# PIC18_breakout.net
KiCad netlist of a schematic drawn in EAGLE
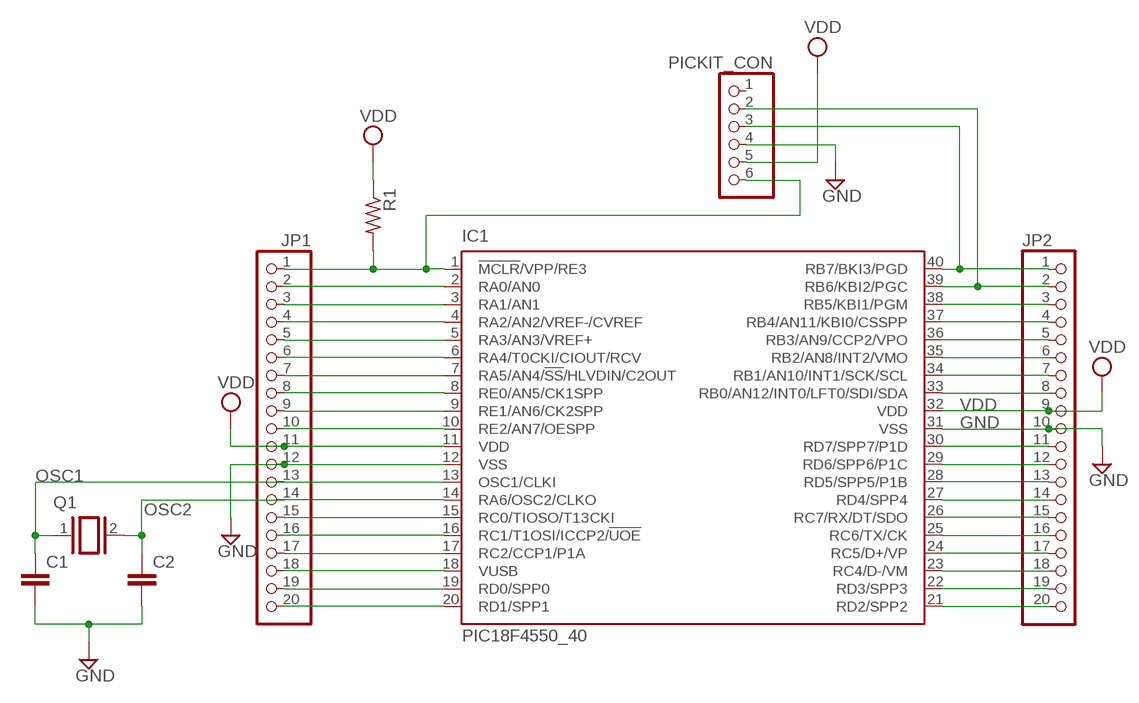
[diagram p0: schematic, sheet 1]

(export (version "E")
  (design (tool "Eeschema 10.0.6"))
  (components
    (comp (ref "C1")
      (value "C-EU075-032X103")
      (footprint "eagle-import:C075-032X103")
      (libsource (lib "eagle-import") (part "C-EU075-032X103"))
    )
    (comp (ref "C2")
      (value "C-EU075-032X103")
      (footprint "eagle-import:C075-032X103")
      (libsource (lib "eagle-import") (part "C-EU075-032X103"))
    )
    (comp (ref "IC1")
      (value "PIC18F4550_40")
      (footprint "eagle-import:DIL40")
      (fields (field (name "MF") "MICROCHIP") (field (name "MPN") "PIC18F4550-I/P"))
      (libsource (lib "eagle-import") (part "PIC18F4_40550"))
    )
    (comp (ref "JP1")
      (value "PINHD-1X20")
      (footprint "eagle-import:1X20")
      (libsource (lib "eagle-import") (part "PINHD-1X20"))
    )
    (comp (ref "JP2")
      (value "PINHD-1X20")
      (footprint "eagle-import:1X20")
      (libsource (lib "eagle-import") (part "PINHD-1X20"))
    )
    (comp (ref "PICKIT_CON")
      (value "PINHD-1X6/90")
      (footprint "eagle-import:1X06_90")
      (libsource (lib "eagle-import") (part "PINHD-1X6/90"))
    )
    (comp (ref "Q1")
      (value "XTAL/S")
      (footprint "eagle-import:QS")
      (libsource (lib "eagle-import") (part "XTAL/S"))
    )
    (comp (ref "R1")
      (value "R-US_0207/10")
      (footprint "eagle-import:0207_10")
      (libsource (lib "eagle-import") (part "R-US_0207/10"))
    )
  )
  (nets
    (net (code "1") (name "/OSC1") (class "Default")
      (node (ref "C1") (pin "1") (pinfunction "1_1") (pintype "passive"))
      (node (ref "IC1") (pin "13") (pinfunction "OSC1/CLKI_13") (pintype "input"))
      (node (ref "JP1") (pin "13") (pinfunction "13_13") (pintype "passive"))
      (node (ref "Q1") (pin "1") (pinfunction "1_1") (pintype "passive"))
    )
    (net (code "2") (name "/OSC2") (class "Default")
      (node (ref "C2") (pin "1") (pinfunction "1_1") (pintype "passive"))
      (node (ref "IC1") (pin "14") (pinfunction "RA6/OSC2/CLKO_14") (pintype "output"))
      (node (ref "JP1") (pin "14") (pinfunction "14_14") (pintype "passive"))
      (node (ref "Q1") (pin "2") (pinfunction "2_2") (pintype "passive"))
    )
    (net (code "3") (name "GND") (class "Default")
      (node (ref "C1") (pin "2") (pinfunction "2_2") (pintype "passive"))
      (node (ref "C2") (pin "2") (pinfunction "2_2") (pintype "passive"))
      (node (ref "IC1") (pin "12") (pinfunction "VSS_12") (pintype "power_in"))
      (node (ref "IC1") (pin "31") (pinfunction "VSS_31") (pintype "power_in"))
      (node (ref "JP1") (pin "12") (pinfunction "12_12") (pintype "passive"))
      (node (ref "JP2") (pin "10") (pinfunction "10_10") (pintype "passive"))
      (node (ref "PICKIT_CON") (pin "4") (pinfunction "4_4") (pintype "passive"))
    )
    (net (code "4") (name "Net-(IC1-RA0{slash}AN0)") (class "Default")
      (node (ref "IC1") (pin "2") (pinfunction "RA0/AN0_2") (pintype "bidirectional"))
      (node (ref "JP1") (pin "2") (pinfunction "2_2") (pintype "passive"))
    )
    (net (code "5") (name "Net-(IC1-RA1{slash}AN1)") (class "Default")
      (node (ref "IC1") (pin "3") (pinfunction "RA1/AN1_3") (pintype "bidirectional"))
      (node (ref "JP1") (pin "3") (pinfunction "3_3") (pintype "passive"))
    )
    (net (code "6") (name "Net-(IC1-RA2{slash}AN2{slash}VREF-{slash}CVREF)") (class "Default")
      (node (ref "IC1") (pin "4") (pinfunction "RA2/AN2/VREF-/CVREF_4") (pintype "bidirectional"))
      (node (ref "JP1") (pin "4") (pinfunction "4_4") (pintype "passive"))
    )
    (net (code "7") (name "Net-(IC1-RA3{slash}AN3{slash}VREF+)") (class "Default")
      (node (ref "IC1") (pin "5") (pinfunction "RA3/AN3/VREF+_5") (pintype "bidirectional"))
      (node (ref "JP1") (pin "5") (pinfunction "5_5") (pintype "passive"))
    )
    (net (code "8") (name "Net-(IC1-RA4{slash}T0CKI{slash}CIOUT{slash}RCV)") (class "Default")
      (node (ref "IC1") (pin "6") (pinfunction "RA4/T0CKI/CIOUT/RCV_6") (pintype "bidirectional"))
      (node (ref "JP1") (pin "6") (pinfunction "6_6") (pintype "passive"))
    )
    (net (code "9") (name "Net-(IC1-RA5{slash}AN4{slash}~{SS}{slash}HLVDIN{slash}C2OUT)") (class "Default")
      (node (ref "IC1") (pin "7") (pinfunction "RA5/AN4/~{SS}/HLVDIN/C2OUT_7") (pintype "bidirectional"))
      (node (ref "JP1") (pin "7") (pinfunction "7_7") (pintype "passive"))
    )
    (net (code "10") (name "Net-(IC1-RB0{slash}AN12{slash}INT0{slash}LFT0{slash}SDI{slash}SDA)") (class "Default")
      (node (ref "IC1") (pin "33") (pinfunction "RB0/AN12/INT0/LFT0/SDI/SDA_33") (pintype "bidirectional"))
      (node (ref "JP2") (pin "8") (pinfunction "8_8") (pintype "passive"))
    )
    (net (code "11") (name "Net-(IC1-RB1{slash}AN10{slash}INT1{slash}SCK{slash}SCL)") (class "Default")
      (node (ref "IC1") (pin "34") (pinfunction "RB1/AN10/INT1/SCK/SCL_34") (pintype "bidirectional"))
      (node (ref "JP2") (pin "7") (pinfunction "7_7") (pintype "passive"))
    )
    (net (code "12") (name "Net-(IC1-RB2{slash}AN8{slash}INT2{slash}VMO)") (class "Default")
      (node (ref "IC1") (pin "35") (pinfunction "RB2/AN8/INT2/VMO_35") (pintype "bidirectional"))
      (node (ref "JP2") (pin "6") (pinfunction "6_6") (pintype "passive"))
    )
    (net (code "13") (name "Net-(IC1-RB3{slash}AN9{slash}CCP2{slash}VPO)") (class "Default")
      (node (ref "IC1") (pin "36") (pinfunction "RB3/AN9/CCP2/VPO_36") (pintype "bidirectional"))
      (node (ref "JP2") (pin "5") (pinfunction "5_5") (pintype "passive"))
    )
    (net (code "14") (name "Net-(IC1-RB4{slash}AN11{slash}KBI0{slash}CSSPP)") (class "Default")
      (node (ref "IC1") (pin "37") (pinfunction "RB4/AN11/KBI0/CSSPP_37") (pintype "bidirectional"))
      (node (ref "JP2") (pin "4") (pinfunction "4_4") (pintype "passive"))
    )
    (net (code "15") (name "Net-(IC1-RB5{slash}KBI1{slash}PGM)") (class "Default")
      (node (ref "IC1") (pin "38") (pinfunction "RB5/KBI1/PGM_38") (pintype "bidirectional"))
      (node (ref "JP2") (pin "3") (pinfunction "3_3") (pintype "passive"))
    )
    (net (code "16") (name "Net-(IC1-RB6{slash}KBI2{slash}PGC)") (class "Default")
      (node (ref "IC1") (pin "39") (pinfunction "RB6/KBI2/PGC_39") (pintype "bidirectional"))
      (node (ref "JP2") (pin "2") (pinfunction "2_2") (pintype "passive"))
      (node (ref "PICKIT_CON") (pin "2") (pinfunction "2_2") (pintype "passive"))
    )
    (net (code "17") (name "Net-(IC1-RB7{slash}BKI3{slash}PGD)") (class "Default")
      (node (ref "IC1") (pin "40") (pinfunction "RB7/BKI3/PGD_40") (pintype "bidirectional"))
      (node (ref "JP2") (pin "1") (pinfunction "1_1") (pintype "passive"))
      (node (ref "PICKIT_CON") (pin "3") (pinfunction "3_3") (pintype "passive"))
    )
    (net (code "18") (name "Net-(IC1-RC0{slash}TIOSO{slash}T13CKI)") (class "Default")
      (node (ref "IC1") (pin "15") (pinfunction "RC0/TIOSO/T13CKI_15") (pintype "bidirectional"))
      (node (ref "JP1") (pin "15") (pinfunction "15_15") (pintype "passive"))
    )
    (net (code "19") (name "Net-(IC1-RC1{slash}T1OSI{slash}ICCP2{slash}~{UOE})") (class "Default")
      (node (ref "IC1") (pin "16") (pinfunction "RC1/T1OSI/ICCP2/~{UOE}_16") (pintype "bidirectional"))
      (node (ref "JP1") (pin "16") (pinfunction "16_16") (pintype "passive"))
    )
    (net (code "20") (name "Net-(IC1-RC2{slash}CCP1{slash}P1A)") (class "Default")
      (node (ref "IC1") (pin "17") (pinfunction "RC2/CCP1/P1A_17") (pintype "bidirectional"))
      (node (ref "JP1") (pin "17") (pinfunction "17_17") (pintype "passive"))
    )
    (net (code "21") (name "Net-(IC1-RC4{slash}D-{slash}VM)") (class "Default")
      (node (ref "IC1") (pin "23") (pinfunction "RC4/D-/VM_23") (pintype "bidirectional"))
      (node (ref "JP2") (pin "18") (pinfunction "18_18") (pintype "passive"))
    )
    (net (code "22") (name "Net-(IC1-RC5{slash}D+{slash}VP)") (class "Default")
      (node (ref "IC1") (pin "24") (pinfunction "RC5/D+/VP_24") (pintype "bidirectional"))
      (node (ref "JP2") (pin "17") (pinfunction "17_17") (pintype "passive"))
    )
    (net (code "23") (name "Net-(IC1-RC6{slash}TX{slash}CK)") (class "Default")
      (node (ref "IC1") (pin "25") (pinfunction "RC6/TX/CK_25") (pintype "bidirectional"))
      (node (ref "JP2") (pin "16") (pinfunction "16_16") (pintype "passive"))
    )
    (net (code "24") (name "Net-(IC1-RC7{slash}RX{slash}DT{slash}SDO)") (class "Default")
      (node (ref "IC1") (pin "26") (pinfunction "RC7/RX/DT/SDO_26") (pintype "bidirectional"))
      (node (ref "JP2") (pin "15") (pinfunction "15_15") (pintype "passive"))
    )
    (net (code "25") (name "Net-(IC1-RD0{slash}SPP0)") (class "Default")
      (node (ref "IC1") (pin "19") (pinfunction "RD0/SPP0_19") (pintype "bidirectional"))
      (node (ref "JP1") (pin "19") (pinfunction "19_19") (pintype "passive"))
    )
    (net (code "26") (name "Net-(IC1-RD1{slash}SPP1)") (class "Default")
      (node (ref "IC1") (pin "20") (pinfunction "RD1/SPP1_20") (pintype "bidirectional"))
      (node (ref "JP1") (pin "20") (pinfunction "20_20") (pintype "passive"))
    )
    (net (code "27") (name "Net-(IC1-RD2{slash}SPP2)") (class "Default")
      (node (ref "IC1") (pin "21") (pinfunction "RD2/SPP2_21") (pintype "bidirectional"))
      (node (ref "JP2") (pin "20") (pinfunction "20_20") (pintype "passive"))
    )
    (net (code "28") (name "Net-(IC1-RD3{slash}SPP3)") (class "Default")
      (node (ref "IC1") (pin "22") (pinfunction "RD3/SPP3_22") (pintype "bidirectional"))
      (node (ref "JP2") (pin "19") (pinfunction "19_19") (pintype "passive"))
    )
    (net (code "29") (name "Net-(IC1-RD4{slash}SPP4)") (class "Default")
      (node (ref "IC1") (pin "27") (pinfunction "RD4/SPP4_27") (pintype "bidirectional"))
      (node (ref "JP2") (pin "14") (pinfunction "14_14") (pintype "passive"))
    )
    (net (code "30") (name "Net-(IC1-RD5{slash}SPP5{slash}P1B)") (class "Default")
      (node (ref "IC1") (pin "28") (pinfunction "RD5/SPP5/P1B_28") (pintype "bidirectional"))
      (node (ref "JP2") (pin "13") (pinfunction "13_13") (pintype "passive"))
    )
    (net (code "31") (name "Net-(IC1-RD6{slash}SPP6{slash}P1C)") (class "Default")
      (node (ref "IC1") (pin "29") (pinfunction "RD6/SPP6/P1C_29") (pintype "bidirectional"))
      (node (ref "JP2") (pin "12") (pinfunction "12_12") (pintype "passive"))
    )
    (net (code "32") (name "Net-(IC1-RD7{slash}SPP7{slash}P1D)") (class "Default")
      (node (ref "IC1") (pin "30") (pinfunction "RD7/SPP7/P1D_30") (pintype "bidirectional"))
      (node (ref "JP2") (pin "11") (pinfunction "11_11") (pintype "passive"))
    )
    (net (code "33") (name "Net-(IC1-RE0{slash}AN5{slash}CK1SPP)") (class "Default")
      (node (ref "IC1") (pin "8") (pinfunction "RE0/AN5/CK1SPP_8") (pintype "bidirectional"))
      (node (ref "JP1") (pin "8") (pinfunction "8_8") (pintype "passive"))
    )
    (net (code "34") (name "Net-(IC1-RE1{slash}AN6{slash}CK2SPP)") (class "Default")
      (node (ref "IC1") (pin "9") (pinfunction "RE1/AN6/CK2SPP_9") (pintype "bidirectional"))
      (node (ref "JP1") (pin "9") (pinfunction "9_9") (pintype "passive"))
    )
    (net (code "35") (name "Net-(IC1-RE2{slash}AN7{slash}OESPP)") (class "Default")
      (node (ref "IC1") (pin "10") (pinfunction "RE2/AN7/OESPP_10") (pintype "bidirectional"))
      (node (ref "JP1") (pin "10") (pinfunction "10_10") (pintype "passive"))
    )
    (net (code "36") (name "Net-(IC1-VUSB)") (class "Default")
      (node (ref "IC1") (pin "18") (pinfunction "VUSB_18") (pintype "bidirectional"))
      (node (ref "JP1") (pin "18") (pinfunction "18_18") (pintype "passive"))
    )
    (net (code "37") (name "Net-(IC1-~{MCLR}{slash}VPP{slash}RE3)") (class "Default")
      (node (ref "IC1") (pin "1") (pinfunction "~{MCLR}/VPP/RE3_1") (pintype "input"))
      (node (ref "JP1") (pin "1") (pinfunction "1_1") (pintype "passive"))
      (node (ref "PICKIT_CON") (pin "6") (pinfunction "6_6") (pintype "passive"))
      (node (ref "R1") (pin "2") (pinfunction "2_2") (pintype "passive"))
    )
    (net (code "38") (name "VDD") (class "Default")
      (node (ref "IC1") (pin "11") (pinfunction "VDD_11") (pintype "power_in"))
      (node (ref "IC1") (pin "32") (pinfunction "VDD_32") (pintype "power_in"))
      (node (ref "JP1") (pin "11") (pinfunction "11_11") (pintype "passive"))
      (node (ref "JP2") (pin "9") (pinfunction "9_9") (pintype "passive"))
      (node (ref "PICKIT_CON") (pin "5") (pinfunction "5_5") (pintype "passive"))
      (node (ref "R1") (pin "1") (pinfunction "1_1") (pintype "passive"))
    )
    (net (code "39") (name "unconnected-(PICKIT_CON-Pad1)") (class "Default")
      (node (ref "PICKIT_CON") (pin "1") (pinfunction "1_1") (pintype "passive"))
    )
  )
)
